# Gamecube3.net
KiCad netlist of a schematic drawn in EAGLE
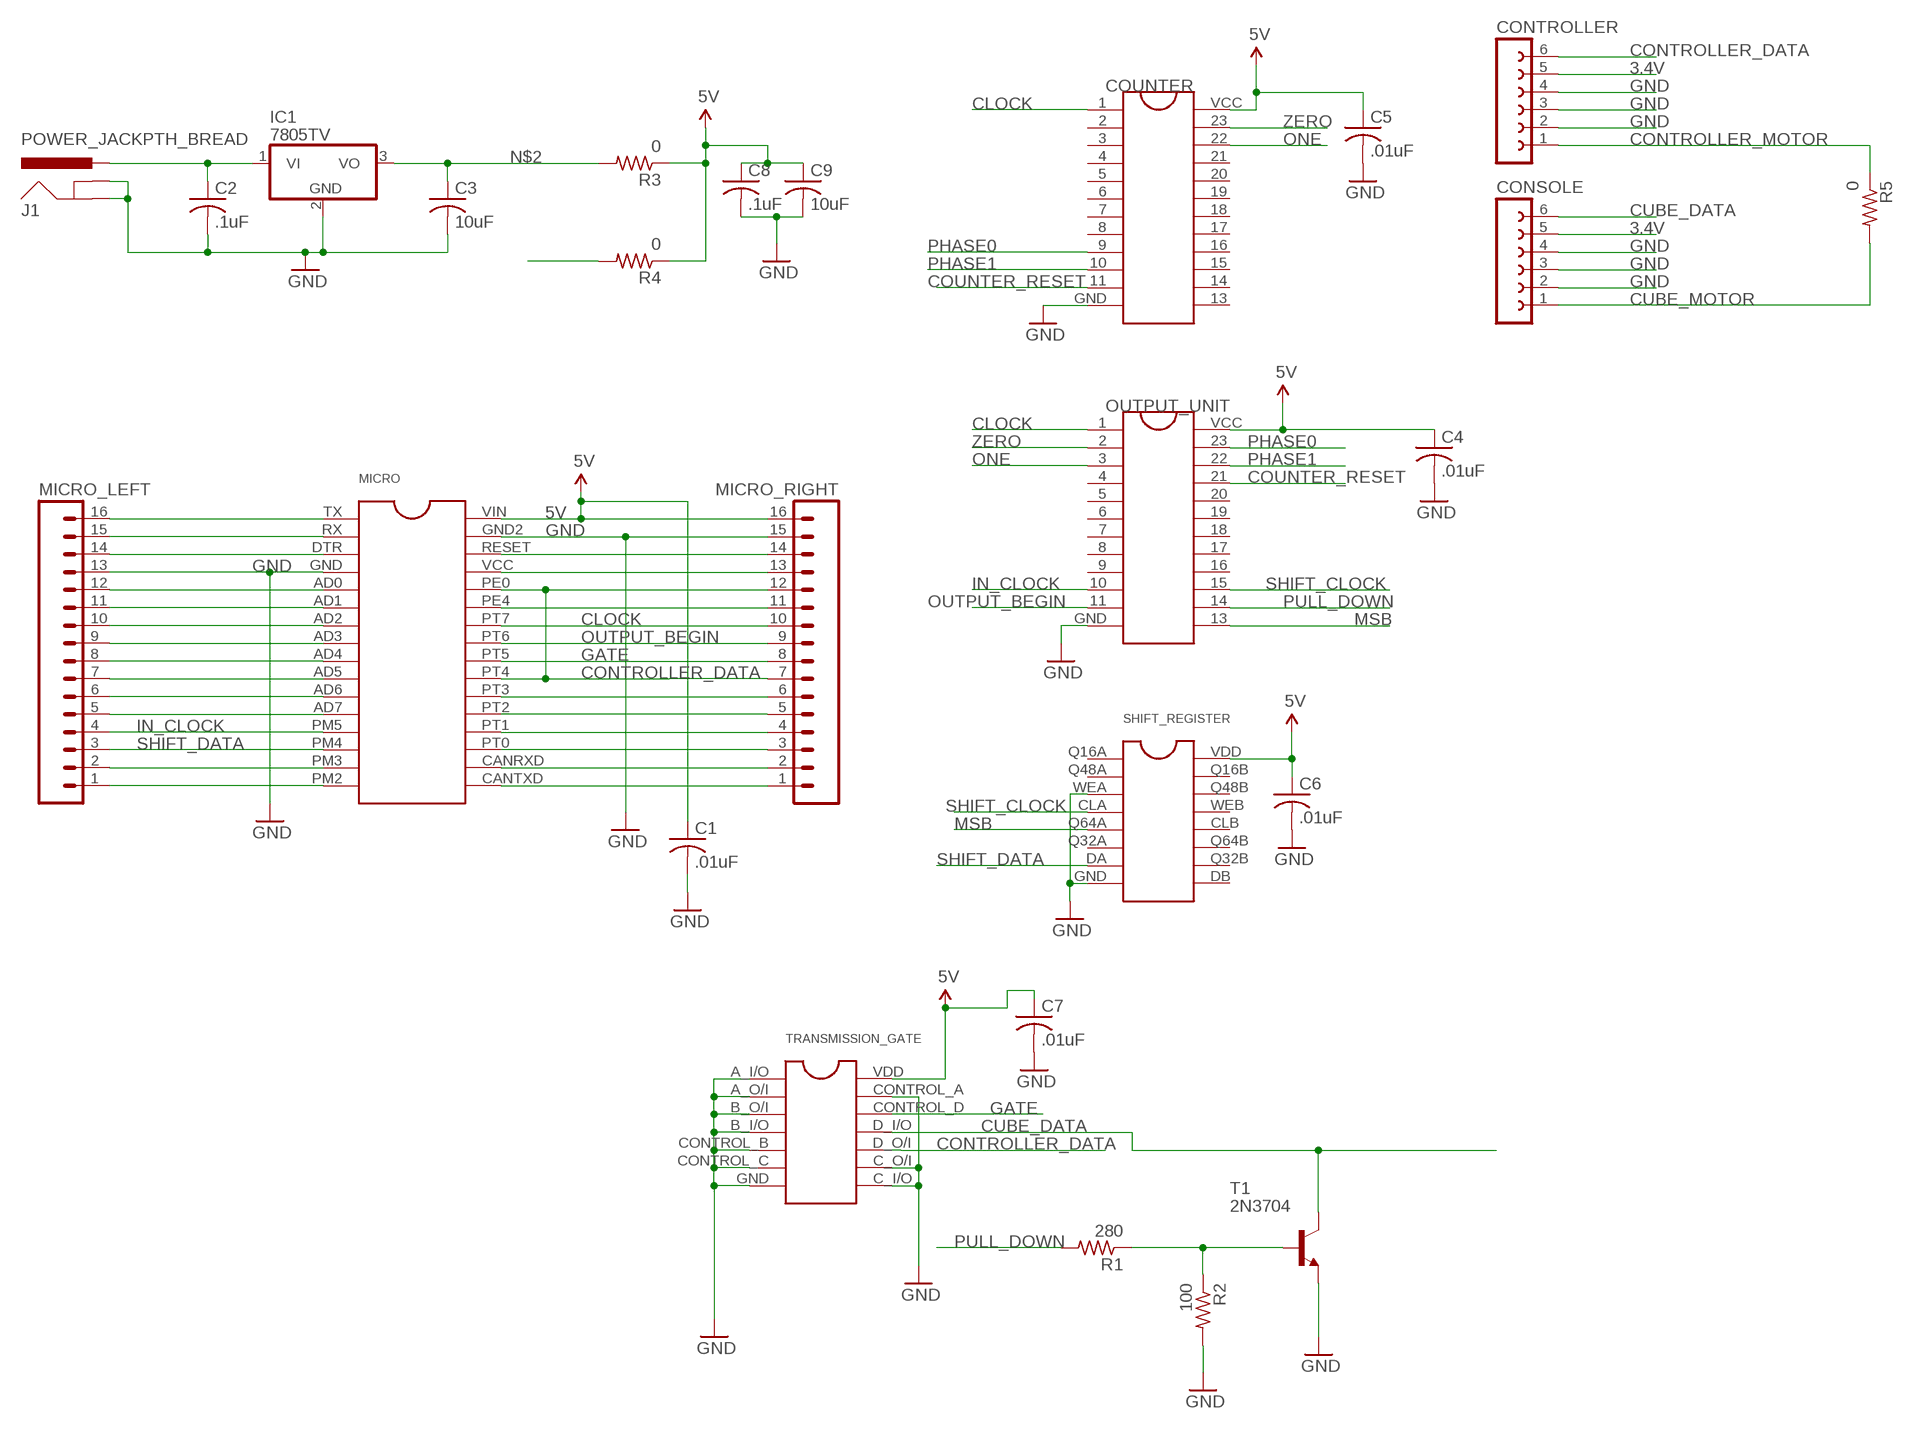
[diagram p0: schematic, sheet 1]

(export (version "E")
  (design (tool "Eeschema 10.0.6"))
  (components
    (comp (ref "C1")
      (value ".01uF")
      (footprint "eagle-import:C0805")
      (libsource (lib "eagle-import") (part "C-USC0805"))
    )
    (comp (ref "C2")
      (value ".1uF")
      (footprint "eagle-import:C0805")
      (libsource (lib "eagle-import") (part "C-USC0805"))
    )
    (comp (ref "C3")
      (value "10uF")
      (footprint "eagle-import:C1206")
      (libsource (lib "eagle-import") (part "C-USC1206"))
    )
    (comp (ref "C4")
      (value ".01uF")
      (footprint "eagle-import:C0805")
      (libsource (lib "eagle-import") (part "C-USC0805"))
    )
    (comp (ref "C5")
      (value ".01uF")
      (footprint "eagle-import:C0805")
      (libsource (lib "eagle-import") (part "C-USC0805"))
    )
    (comp (ref "C6")
      (value ".01uF")
      (footprint "eagle-import:C0805")
      (libsource (lib "eagle-import") (part "C-USC0805"))
    )
    (comp (ref "C7")
      (value ".01uF")
      (footprint "eagle-import:C0805")
      (libsource (lib "eagle-import") (part "C-USC0805"))
    )
    (comp (ref "C8")
      (value ".1uF")
      (footprint "eagle-import:C0805")
      (libsource (lib "eagle-import") (part "C-USC0805"))
    )
    (comp (ref "C9")
      (value "10uF")
      (footprint "eagle-import:C1206")
      (libsource (lib "eagle-import") (part "C-USC1206"))
    )
    (comp (ref "CONSOLE")
      (value "FE06-1")
      (footprint "eagle-import:FE06")
      (libsource (lib "eagle-import") (part "FE06-1"))
    )
    (comp (ref "CONTROLLER")
      (value "FE06-1")
      (footprint "eagle-import:FE06")
      (libsource (lib "eagle-import") (part "FE06-1"))
    )
    (comp (ref "COUNTER")
      (value "GAL22V10")
      (footprint "eagle-import:24-PIN-DIP")
      (libsource (lib "eagle-import") (part "GAL22V10"))
    )
    (comp (ref "IC1")
      (value "7805TV")
      (footprint "eagle-import:TO220V")
      (libsource (lib "eagle-import") (part "78TV05"))
    )
    (comp (ref "J1")
      (value "POWER_JACKPTH_BREAD")
      (footprint "eagle-import:POWER_JACK_PTH_BREAD")
      (libsource (lib "eagle-import") (part "POWER_JACKPTH_BREAD"))
    )
    (comp (ref "MICRO")
      (value "9S12C32")
      (footprint "eagle-import:9S12-32PIN-DIP")
      (libsource (lib "eagle-import") (part "9S12C32"))
    )
    (comp (ref "MICRO_LEFT")
      (value "M16")
      (footprint "eagle-import:16P")
      (libsource (lib "eagle-import") (part "M16"))
    )
    (comp (ref "MICRO_RIGHT")
      (value "M16")
      (footprint "eagle-import:16P")
      (libsource (lib "eagle-import") (part "M16"))
    )
    (comp (ref "OUTPUT_UNIT")
      (value "GAL22V10")
      (footprint "eagle-import:24-PIN-DIP")
      (libsource (lib "eagle-import") (part "GAL22V10"))
    )
    (comp (ref "R1")
      (value "280")
      (footprint "eagle-import:0204_7")
      (libsource (lib "eagle-import") (part "R-US_0204/7"))
    )
    (comp (ref "R2")
      (value "100")
      (footprint "eagle-import:0204_7")
      (libsource (lib "eagle-import") (part "R-US_0204/7"))
    )
    (comp (ref "R3")
      (value "0")
      (footprint "eagle-import:0204_7")
      (libsource (lib "eagle-import") (part "R-US_0204/7"))
    )
    (comp (ref "R4")
      (value "0")
      (footprint "eagle-import:0204_7")
      (libsource (lib "eagle-import") (part "R-US_0204/7"))
    )
    (comp (ref "R5")
      (value "0")
      (footprint "eagle-import:0204_7")
      (libsource (lib "eagle-import") (part "R-US_0204/7"))
    )
    (comp (ref "SHIFT_REGISTER")
      (value "CD4517B")
      (footprint "eagle-import:CD4517B")
      (libsource (lib "eagle-import") (part "CD4517B"))
    )
    (comp (ref "T1")
      (value "2N3704")
      (footprint "eagle-import:TO92")
      (libsource (lib "eagle-import") (part "2N3704"))
    )
    (comp (ref "TRANSMISSION_GATE")
      (value "CD4066B")
      (footprint "eagle-import:CD4066B")
      (libsource (lib "eagle-import") (part "CD4066B"))
    )
  )
  (nets
    (net (code "1") (name "/3.4V") (class "Default")
      (node (ref "CONSOLE") (pin "5") (pinfunction "5_5") (pintype "passive"))
      (node (ref "CONTROLLER") (pin "5") (pinfunction "5_5") (pintype "passive"))
    )
    (net (code "2") (name "/CLOCK") (class "Default")
      (node (ref "COUNTER") (pin "1") (pinfunction "1_1") (pintype "bidirectional"))
      (node (ref "MICRO") (pin "PT7") (pinfunction "P$26_PT7") (pintype "bidirectional"))
      (node (ref "MICRO_RIGHT") (pin "10") (pinfunction "10_10") (pintype "passive"))
      (node (ref "OUTPUT_UNIT") (pin "1") (pinfunction "1_1") (pintype "bidirectional"))
    )
    (net (code "3") (name "/CONTROLLER_DATA") (class "Default")
      (node (ref "CONTROLLER") (pin "6") (pinfunction "6_6") (pintype "passive"))
      (node (ref "MICRO") (pin "PE0") (pinfunction "P$28_PE0") (pintype "bidirectional"))
      (node (ref "MICRO") (pin "PT4") (pinfunction "P$23_PT4") (pintype "bidirectional"))
      (node (ref "MICRO_RIGHT") (pin "12") (pinfunction "12_12") (pintype "passive"))
      (node (ref "MICRO_RIGHT") (pin "7") (pinfunction "7_7") (pintype "passive"))
      (node (ref "TRANSMISSION_GATE") (pin "D_O/I") (pinfunction "P$10_D_O/I") (pintype "bidirectional"))
    )
    (net (code "4") (name "/CONTROLLER_MOTOR") (class "Default")
      (node (ref "CONTROLLER") (pin "1") (pinfunction "1_1") (pintype "passive"))
      (node (ref "R5") (pin "1") (pinfunction "1_1") (pintype "passive"))
    )
    (net (code "5") (name "/COUNTER_RESET") (class "Default")
      (node (ref "COUNTER") (pin "11") (pinfunction "11_11") (pintype "bidirectional"))
      (node (ref "OUTPUT_UNIT") (pin "21") (pinfunction "21_21") (pintype "bidirectional"))
    )
    (net (code "6") (name "/CUBE_DATA") (class "Default")
      (node (ref "CONSOLE") (pin "6") (pinfunction "6_6") (pintype "passive"))
      (node (ref "T1") (pin "2") (pinfunction "C_2") (pintype "passive"))
      (node (ref "TRANSMISSION_GATE") (pin "D_I/O") (pinfunction "P$11_D_I/O") (pintype "bidirectional"))
    )
    (net (code "7") (name "/CUBE_MOTOR") (class "Default")
      (node (ref "CONSOLE") (pin "1") (pinfunction "1_1") (pintype "passive"))
      (node (ref "R4") (pin "2") (pinfunction "2_2") (pintype "passive"))
      (node (ref "R5") (pin "2") (pinfunction "2_2") (pintype "passive"))
    )
    (net (code "8") (name "/GATE") (class "Default")
      (node (ref "MICRO") (pin "PT5") (pinfunction "P$24_PT5") (pintype "bidirectional"))
      (node (ref "MICRO_RIGHT") (pin "8") (pinfunction "8_8") (pintype "passive"))
      (node (ref "TRANSMISSION_GATE") (pin "CONTROL_D") (pinfunction "P$12_CONTROL_D") (pintype "bidirectional"))
    )
    (net (code "9") (name "/IN_CLOCK") (class "Default")
      (node (ref "MICRO") (pin "PM5") (pinfunction "P$13_PM5") (pintype "bidirectional"))
      (node (ref "MICRO_LEFT") (pin "4") (pinfunction "4_4") (pintype "passive"))
      (node (ref "OUTPUT_UNIT") (pin "10") (pinfunction "10_10") (pintype "bidirectional"))
    )
    (net (code "10") (name "/MSB") (class "Default")
      (node (ref "OUTPUT_UNIT") (pin "13") (pinfunction "13_13") (pintype "bidirectional"))
      (node (ref "SHIFT_REGISTER") (pin "Q64A") (pinfunction "P$5_Q64A") (pintype "bidirectional"))
    )
    (net (code "11") (name "/N$2") (class "Default")
      (node (ref "C3") (pin "1") (pinfunction "1_1") (pintype "passive"))
      (node (ref "IC1") (pin "3") (pinfunction "VO_3") (pintype "passive"))
      (node (ref "R3") (pin "2") (pinfunction "2_2") (pintype "passive"))
    )
    (net (code "12") (name "/ONE") (class "Default")
      (node (ref "COUNTER") (pin "22") (pinfunction "22_22") (pintype "bidirectional"))
      (node (ref "OUTPUT_UNIT") (pin "3") (pinfunction "3_3") (pintype "bidirectional"))
    )
    (net (code "13") (name "/OUTPUT_BEGIN") (class "Default")
      (node (ref "MICRO") (pin "PT6") (pinfunction "P$25_PT6") (pintype "bidirectional"))
      (node (ref "MICRO_RIGHT") (pin "9") (pinfunction "9_9") (pintype "passive"))
      (node (ref "OUTPUT_UNIT") (pin "11") (pinfunction "11_11") (pintype "bidirectional"))
    )
    (net (code "14") (name "/PHASE0") (class "Default")
      (node (ref "COUNTER") (pin "9") (pinfunction "9_9") (pintype "bidirectional"))
      (node (ref "OUTPUT_UNIT") (pin "23") (pinfunction "23_23") (pintype "bidirectional"))
    )
    (net (code "15") (name "/PHASE1") (class "Default")
      (node (ref "COUNTER") (pin "10") (pinfunction "10_10") (pintype "bidirectional"))
      (node (ref "OUTPUT_UNIT") (pin "22") (pinfunction "22_22") (pintype "bidirectional"))
    )
    (net (code "16") (name "/PULL_DOWN") (class "Default")
      (node (ref "OUTPUT_UNIT") (pin "14") (pinfunction "14_14") (pintype "bidirectional"))
      (node (ref "R1") (pin "2") (pinfunction "2_2") (pintype "passive"))
    )
    (net (code "17") (name "/SHIFT_CLOCK") (class "Default")
      (node (ref "OUTPUT_UNIT") (pin "15") (pinfunction "15_15") (pintype "bidirectional"))
      (node (ref "SHIFT_REGISTER") (pin "CLA") (pinfunction "P$4_CLA") (pintype "bidirectional"))
    )
    (net (code "18") (name "/SHIFT_DATA") (class "Default")
      (node (ref "MICRO") (pin "PM4") (pinfunction "P$14_PM4") (pintype "bidirectional"))
      (node (ref "MICRO_LEFT") (pin "3") (pinfunction "3_3") (pintype "passive"))
      (node (ref "SHIFT_REGISTER") (pin "DA") (pinfunction "P$7_DA") (pintype "bidirectional"))
    )
    (net (code "19") (name "/ZERO") (class "Default")
      (node (ref "COUNTER") (pin "23") (pinfunction "23_23") (pintype "bidirectional"))
      (node (ref "OUTPUT_UNIT") (pin "2") (pinfunction "2_2") (pintype "bidirectional"))
    )
    (net (code "20") (name "5V") (class "Default")
      (node (ref "C1") (pin "1") (pinfunction "1_1") (pintype "passive"))
      (node (ref "C4") (pin "1") (pinfunction "1_1") (pintype "passive"))
      (node (ref "C5") (pin "1") (pinfunction "1_1") (pintype "passive"))
      (node (ref "C6") (pin "1") (pinfunction "1_1") (pintype "passive"))
      (node (ref "C7") (pin "1") (pinfunction "1_1") (pintype "passive"))
      (node (ref "C8") (pin "1") (pinfunction "1_1") (pintype "passive"))
      (node (ref "C9") (pin "1") (pinfunction "1_1") (pintype "passive"))
      (node (ref "COUNTER") (pin "VCC") (pinfunction "VCC_VCC") (pintype "bidirectional"))
      (node (ref "MICRO") (pin "VIN") (pinfunction "P$32_VIN") (pintype "bidirectional"))
      (node (ref "MICRO_RIGHT") (pin "16") (pinfunction "16_16") (pintype "passive"))
      (node (ref "OUTPUT_UNIT") (pin "VCC") (pinfunction "VCC_VCC") (pintype "bidirectional"))
      (node (ref "R3") (pin "1") (pinfunction "1_1") (pintype "passive"))
      (node (ref "R4") (pin "1") (pinfunction "1_1") (pintype "passive"))
      (node (ref "SHIFT_REGISTER") (pin "VDD") (pinfunction "P$16_VDD") (pintype "bidirectional"))
      (node (ref "TRANSMISSION_GATE") (pin "VDD") (pinfunction "P$14_VDD") (pintype "bidirectional"))
    )
    (net (code "21") (name "GND") (class "Default")
      (node (ref "C1") (pin "2") (pinfunction "2_2") (pintype "passive"))
      (node (ref "C2") (pin "2") (pinfunction "2_2") (pintype "passive"))
      (node (ref "C3") (pin "2") (pinfunction "2_2") (pintype "passive"))
      (node (ref "C4") (pin "2") (pinfunction "2_2") (pintype "passive"))
      (node (ref "C5") (pin "2") (pinfunction "2_2") (pintype "passive"))
      (node (ref "C6") (pin "2") (pinfunction "2_2") (pintype "passive"))
      (node (ref "C7") (pin "2") (pinfunction "2_2") (pintype "passive"))
      (node (ref "C8") (pin "2") (pinfunction "2_2") (pintype "passive"))
      (node (ref "C9") (pin "2") (pinfunction "2_2") (pintype "passive"))
      (node (ref "CONSOLE") (pin "2") (pinfunction "2_2") (pintype "passive"))
      (node (ref "CONSOLE") (pin "3") (pinfunction "3_3") (pintype "passive"))
      (node (ref "CONSOLE") (pin "4") (pinfunction "4_4") (pintype "passive"))
      (node (ref "CONTROLLER") (pin "2") (pinfunction "2_2") (pintype "passive"))
      (node (ref "CONTROLLER") (pin "3") (pinfunction "3_3") (pintype "passive"))
      (node (ref "CONTROLLER") (pin "4") (pinfunction "4_4") (pintype "passive"))
      (node (ref "COUNTER") (pin "GND") (pinfunction "GND_GND") (pintype "bidirectional"))
      (node (ref "IC1") (pin "2") (pinfunction "GND_2") (pintype "passive"))
      (node (ref "J1") (pin "GND") (pinfunction "GND_GND") (pintype "bidirectional"))
      (node (ref "J1") (pin "GNDBREAK") (pinfunction "GNDBREAK_GNDBREAK") (pintype "bidirectional"))
      (node (ref "MICRO") (pin "GND") (pinfunction "P$4_GND") (pintype "bidirectional"))
      (node (ref "MICRO") (pin "GND2") (pinfunction "P$31_GND2") (pintype "bidirectional"))
      (node (ref "MICRO_LEFT") (pin "13") (pinfunction "13_13") (pintype "passive"))
      (node (ref "MICRO_RIGHT") (pin "15") (pinfunction "15_15") (pintype "passive"))
      (node (ref "OUTPUT_UNIT") (pin "GND") (pinfunction "GND_GND") (pintype "bidirectional"))
      (node (ref "R2") (pin "2") (pinfunction "2_2") (pintype "passive"))
      (node (ref "SHIFT_REGISTER") (pin "GND") (pinfunction "P$8_GND") (pintype "bidirectional"))
      (node (ref "SHIFT_REGISTER") (pin "WEA") (pinfunction "P$3_WEA") (pintype "bidirectional"))
      (node (ref "T1") (pin "3") (pinfunction "E_3") (pintype "passive"))
      (node (ref "TRANSMISSION_GATE") (pin "A_I/O") (pinfunction "P$1_A_I/O") (pintype "bidirectional"))
      (node (ref "TRANSMISSION_GATE") (pin "A_O/I") (pinfunction "P$2_A_O/I") (pintype "bidirectional"))
      (node (ref "TRANSMISSION_GATE") (pin "B_I/O") (pinfunction "P$4_B_I/O") (pintype "bidirectional"))
      (node (ref "TRANSMISSION_GATE") (pin "B_O/I") (pinfunction "P$3_B_O/I") (pintype "bidirectional"))
      (node (ref "TRANSMISSION_GATE") (pin "CONTROL_A") (pinfunction "P$13_CONTROL_A") (pintype "bidirectional"))
      (node (ref "TRANSMISSION_GATE") (pin "CONTROL_B") (pinfunction "P$5_CONTROL_B") (pintype "bidirectional"))
      (node (ref "TRANSMISSION_GATE") (pin "CONTROL_C") (pinfunction "P$6_CONTROL_C") (pintype "bidirectional"))
      (node (ref "TRANSMISSION_GATE") (pin "C_I/O") (pinfunction "P$8_C_I/O") (pintype "bidirectional"))
      (node (ref "TRANSMISSION_GATE") (pin "C_O/I") (pinfunction "P$9_C_O/I") (pintype "bidirectional"))
      (node (ref "TRANSMISSION_GATE") (pin "GND") (pinfunction "P$7_GND") (pintype "bidirectional"))
    )
    (net (code "22") (name "Net-(IC1-VI)") (class "Default")
      (node (ref "C2") (pin "1") (pinfunction "1_1") (pintype "passive"))
      (node (ref "IC1") (pin "1") (pinfunction "VI_1") (pintype "input"))
      (node (ref "J1") (pin "PWR") (pinfunction "PWR_PWR") (pintype "bidirectional"))
    )
    (net (code "23") (name "Net-(MICRO-P$1)") (class "Default")
      (node (ref "MICRO") (pin "TX") (pinfunction "P$1_TX") (pintype "bidirectional"))
      (node (ref "MICRO_LEFT") (pin "16") (pinfunction "16_16") (pintype "passive"))
    )
    (net (code "24") (name "Net-(MICRO-P$2)") (class "Default")
      (node (ref "MICRO") (pin "RX") (pinfunction "P$2_RX") (pintype "bidirectional"))
      (node (ref "MICRO_LEFT") (pin "15") (pinfunction "15_15") (pintype "passive"))
    )
    (net (code "25") (name "Net-(MICRO-P$3)") (class "Default")
      (node (ref "MICRO") (pin "DTR") (pinfunction "P$3_DTR") (pintype "bidirectional"))
      (node (ref "MICRO_LEFT") (pin "14") (pinfunction "14_14") (pintype "passive"))
    )
    (net (code "26") (name "Net-(MICRO-P$5)") (class "Default")
      (node (ref "MICRO") (pin "AD0") (pinfunction "P$5_AD0") (pintype "bidirectional"))
      (node (ref "MICRO_LEFT") (pin "12") (pinfunction "12_12") (pintype "passive"))
    )
    (net (code "27") (name "Net-(MICRO-P$6)") (class "Default")
      (node (ref "MICRO") (pin "AD1") (pinfunction "P$6_AD1") (pintype "bidirectional"))
      (node (ref "MICRO_LEFT") (pin "11") (pinfunction "11_11") (pintype "passive"))
    )
    (net (code "28") (name "Net-(MICRO-P$7)") (class "Default")
      (node (ref "MICRO") (pin "AD2") (pinfunction "P$7_AD2") (pintype "bidirectional"))
      (node (ref "MICRO_LEFT") (pin "10") (pinfunction "10_10") (pintype "passive"))
    )
    (net (code "29") (name "Net-(MICRO-P$8)") (class "Default")
      (node (ref "MICRO") (pin "AD3") (pinfunction "P$8_AD3") (pintype "bidirectional"))
      (node (ref "MICRO_LEFT") (pin "9") (pinfunction "9_9") (pintype "passive"))
    )
    (net (code "30") (name "Net-(MICRO-P$9)") (class "Default")
      (node (ref "MICRO") (pin "AD4") (pinfunction "P$9_AD4") (pintype "bidirectional"))
      (node (ref "MICRO_LEFT") (pin "8") (pinfunction "8_8") (pintype "passive"))
    )
    (net (code "31") (name "Net-(MICRO-P$10)") (class "Default")
      (node (ref "MICRO") (pin "AD5") (pinfunction "P$10_AD5") (pintype "bidirectional"))
      (node (ref "MICRO_LEFT") (pin "7") (pinfunction "7_7") (pintype "passive"))
    )
    (net (code "32") (name "Net-(MICRO-P$11)") (class "Default")
      (node (ref "MICRO") (pin "AD6") (pinfunction "P$11_AD6") (pintype "bidirectional"))
      (node (ref "MICRO_LEFT") (pin "6") (pinfunction "6_6") (pintype "passive"))
    )
    (net (code "33") (name "Net-(MICRO-P$12)") (class "Default")
      (node (ref "MICRO") (pin "AD7") (pinfunction "P$12_AD7") (pintype "bidirectional"))
      (node (ref "MICRO_LEFT") (pin "5") (pinfunction "5_5") (pintype "passive"))
    )
    (net (code "34") (name "Net-(MICRO-P$15)") (class "Default")
      (node (ref "MICRO") (pin "PM3") (pinfunction "P$15_PM3") (pintype "bidirectional"))
      (node (ref "MICRO_LEFT") (pin "2") (pinfunction "2_2") (pintype "passive"))
    )
    (net (code "35") (name "Net-(MICRO-P$16)") (class "Default")
      (node (ref "MICRO") (pin "PM2") (pinfunction "P$16_PM2") (pintype "bidirectional"))
      (node (ref "MICRO_LEFT") (pin "1") (pinfunction "1_1") (pintype "passive"))
    )
    (net (code "36") (name "Net-(MICRO-P$17)") (class "Default")
      (node (ref "MICRO") (pin "CANTXD") (pinfunction "P$17_CANTXD") (pintype "bidirectional"))
      (node (ref "MICRO_RIGHT") (pin "1") (pinfunction "1_1") (pintype "passive"))
    )
    (net (code "37") (name "Net-(MICRO-P$18)") (class "Default")
      (node (ref "MICRO") (pin "CANRXD") (pinfunction "P$18_CANRXD") (pintype "bidirectional"))
      (node (ref "MICRO_RIGHT") (pin "2") (pinfunction "2_2") (pintype "passive"))
    )
    (net (code "38") (name "Net-(MICRO-P$19)") (class "Default")
      (node (ref "MICRO") (pin "PT0") (pinfunction "P$19_PT0") (pintype "bidirectional"))
      (node (ref "MICRO_RIGHT") (pin "3") (pinfunction "3_3") (pintype "passive"))
    )
    (net (code "39") (name "Net-(MICRO-P$20)") (class "Default")
      (node (ref "MICRO") (pin "PT1") (pinfunction "P$20_PT1") (pintype "bidirectional"))
      (node (ref "MICRO_RIGHT") (pin "4") (pinfunction "4_4") (pintype "passive"))
    )
    (net (code "40") (name "Net-(MICRO-P$21)") (class "Default")
      (node (ref "MICRO") (pin "PT2") (pinfunction "P$21_PT2") (pintype "bidirectional"))
      (node (ref "MICRO_RIGHT") (pin "5") (pinfunction "5_5") (pintype "passive"))
    )
    (net (code "41") (name "Net-(MICRO-P$22)") (class "Default")
      (node (ref "MICRO") (pin "PT3") (pinfunction "P$22_PT3") (pintype "bidirectional"))
      (node (ref "MICRO_RIGHT") (pin "6") (pinfunction "6_6") (pintype "passive"))
    )
    (net (code "42") (name "Net-(MICRO-P$27)") (class "Default")
      (node (ref "MICRO") (pin "PE4") (pinfunction "P$27_PE4") (pintype "bidirectional"))
      (node (ref "MICRO_RIGHT") (pin "11") (pinfunction "11_11") (pintype "passive"))
    )
    (net (code "43") (name "Net-(MICRO-P$29)") (class "Default")
      (node (ref "MICRO") (pin "VCC") (pinfunction "P$29_VCC") (pintype "bidirectional"))
      (node (ref "MICRO_RIGHT") (pin "13") (pinfunction "13_13") (pintype "passive"))
    )
    (net (code "44") (name "Net-(MICRO-P$30)") (class "Default")
      (node (ref "MICRO") (pin "RESET") (pinfunction "P$30_RESET") (pintype "bidirectional"))
      (node (ref "MICRO_RIGHT") (pin "14") (pinfunction "14_14") (pintype "passive"))
    )
    (net (code "45") (name "Net-(T1-B)") (class "Default")
      (node (ref "R1") (pin "1") (pinfunction "1_1") (pintype "passive"))
      (node (ref "R2") (pin "1") (pinfunction "1_1") (pintype "passive"))
      (node (ref "T1") (pin "1") (pinfunction "B_1") (pintype "passive"))
    )
    (net (code "46") (name "unconnected-(COUNTER-Pad2)") (class "Default")
      (node (ref "COUNTER") (pin "2") (pinfunction "2_2") (pintype "bidirectional"))
    )
    (net (code "47") (name "unconnected-(COUNTER-Pad3)") (class "Default")
      (node (ref "COUNTER") (pin "3") (pinfunction "3_3") (pintype "bidirectional"))
    )
    (net (code "48") (name "unconnected-(COUNTER-Pad4)") (class "Default")
      (node (ref "COUNTER") (pin "4") (pinfunction "4_4") (pintype "bidirectional"))
    )
    (net (code "49") (name "unconnected-(COUNTER-Pad5)") (class "Default")
      (node (ref "COUNTER") (pin "5") (pinfunction "5_5") (pintype "bidirectional"))
    )
    (net (code "50") (name "unconnected-(COUNTER-Pad6)") (class "Default")
      (node (ref "COUNTER") (pin "6") (pinfunction "6_6") (pintype "bidirectional"))
    )
    (net (code "51") (name "unconnected-(COUNTER-Pad7)") (class "Default")
      (node (ref "COUNTER") (pin "7") (pinfunction "7_7") (pintype "bidirectional"))
    )
    (net (code "52") (name "unconnected-(COUNTER-Pad8)") (class "Default")
      (node (ref "COUNTER") (pin "8") (pinfunction "8_8") (pintype "bidirectional"))
    )
    (net (code "53") (name "unconnected-(COUNTER-Pad13)") (class "Default")
      (node (ref "COUNTER") (pin "13") (pinfunction "13_13") (pintype "bidirectional"))
    )
    (net (code "54") (name "unconnected-(COUNTER-Pad14)") (class "Default")
      (node (ref "COUNTER") (pin "14") (pinfunction "14_14") (pintype "bidirectional"))
    )
    (net (code "55") (name "unconnected-(COUNTER-Pad15)") (class "Default")
      (node (ref "COUNTER") (pin "15") (pinfunction "15_15") (pintype "bidirectional"))
    )
    (net (code "56") (name "unconnected-(COUNTER-Pad16)") (class "Default")
      (node (ref "COUNTER") (pin "16") (pinfunction "16_16") (pintype "bidirectional"))
    )
    (net (code "57") (name "unconnected-(COUNTER-Pad17)") (class "Default")
      (node (ref "COUNTER") (pin "17") (pinfunction "17_17") (pintype "bidirectional"))
    )
    (net (code "58") (name "unconnected-(COUNTER-Pad18)") (class "Default")
      (node (ref "COUNTER") (pin "18") (pinfunction "18_18") (pintype "bidirectional"))
    )
    (net (code "59") (name "unconnected-(COUNTER-Pad19)") (class "Default")
      (node (ref "COUNTER") (pin "19") (pinfunction "19_19") (pintype "bidirectional"))
    )
    (net (code "60") (name "unconnected-(COUNTER-Pad20)") (class "Default")
      (node (ref "COUNTER") (pin "20") (pinfunction "20_20") (pintype "bidirectional"))
    )
    (net (code "61") (name "unconnected-(COUNTER-Pad21)") (class "Default")
      (node (ref "COUNTER") (pin "21") (pinfunction "21_21") (pintype "bidirectional"))
    )
    (net (code "62") (name "unconnected-(OUTPUT_UNIT-Pad4)") (class "Default")
      (node (ref "OUTPUT_UNIT") (pin "4") (pinfunction "4_4") (pintype "bidirectional"))
    )
    (net (code "63") (name "unconnected-(OUTPUT_UNIT-Pad5)") (class "Default")
      (node (ref "OUTPUT_UNIT") (pin "5") (pinfunction "5_5") (pintype "bidirectional"))
    )
    (net (code "64") (name "unconnected-(OUTPUT_UNIT-Pad6)") (class "Default")
      (node (ref "OUTPUT_UNIT") (pin "6") (pinfunction "6_6") (pintype "bidirectional"))
    )
    (net (code "65") (name "unconnected-(OUTPUT_UNIT-Pad7)") (class "Default")
      (node (ref "OUTPUT_UNIT") (pin "7") (pinfunction "7_7") (pintype "bidirectional"))
    )
    (net (code "66") (name "unconnected-(OUTPUT_UNIT-Pad8)") (class "Default")
      (node (ref "OUTPUT_UNIT") (pin "8") (pinfunction "8_8") (pintype "bidirectional"))
    )
    (net (code "67") (name "unconnected-(OUTPUT_UNIT-Pad9)") (class "Default")
      (node (ref "OUTPUT_UNIT") (pin "9") (pinfunction "9_9") (pintype "bidirectional"))
    )
    (net (code "68") (name "unconnected-(OUTPUT_UNIT-Pad16)") (class "Default")
      (node (ref "OUTPUT_UNIT") (pin "16") (pinfunction "16_16") (pintype "bidirectional"))
    )
    (net (code "69") (name "unconnected-(OUTPUT_UNIT-Pad17)") (class "Default")
      (node (ref "OUTPUT_UNIT") (pin "17") (pinfunction "17_17") (pintype "bidirectional"))
    )
    (net (code "70") (name "unconnected-(OUTPUT_UNIT-Pad18)") (class "Default")
      (node (ref "OUTPUT_UNIT") (pin "18") (pinfunction "18_18") (pintype "bidirectional"))
    )
    (net (code "71") (name "unconnected-(OUTPUT_UNIT-Pad19)") (class "Default")
      (node (ref "OUTPUT_UNIT") (pin "19") (pinfunction "19_19") (pintype "bidirectional"))
    )
    (net (code "72") (name "unconnected-(OUTPUT_UNIT-Pad20)") (class "Default")
      (node (ref "OUTPUT_UNIT") (pin "20") (pinfunction "20_20") (pintype "bidirectional"))
    )
    (net (code "73") (name "unconnected-(SHIFT_REGISTER-P$1-PadQ16A)") (class "Default")
      (node (ref "SHIFT_REGISTER") (pin "Q16A") (pinfunction "P$1_Q16A") (pintype "bidirectional"))
    )
    (net (code "74") (name "unconnected-(SHIFT_REGISTER-P$2-PadQ48A)") (class "Default")
      (node (ref "SHIFT_REGISTER") (pin "Q48A") (pinfunction "P$2_Q48A") (pintype "bidirectional"))
    )
    (net (code "75") (name "unconnected-(SHIFT_REGISTER-P$6-PadQ32A)") (class "Default")
      (node (ref "SHIFT_REGISTER") (pin "Q32A") (pinfunction "P$6_Q32A") (pintype "bidirectional"))
    )
    (net (code "76") (name "unconnected-(SHIFT_REGISTER-P$9-PadDB)") (class "Default")
      (node (ref "SHIFT_REGISTER") (pin "DB") (pinfunction "P$9_DB") (pintype "bidirectional"))
    )
    (net (code "77") (name "unconnected-(SHIFT_REGISTER-P$10-PadQ32B)") (class "Default")
      (node (ref "SHIFT_REGISTER") (pin "Q32B") (pinfunction "P$10_Q32B") (pintype "bidirectional"))
    )
    (net (code "78") (name "unconnected-(SHIFT_REGISTER-P$11-PadQ64B)") (class "Default")
      (node (ref "SHIFT_REGISTER") (pin "Q64B") (pinfunction "P$11_Q64B") (pintype "bidirectional"))
    )
    (net (code "79") (name "unconnected-(SHIFT_REGISTER-P$12-PadCLB)") (class "Default")
      (node (ref "SHIFT_REGISTER") (pin "CLB") (pinfunction "P$12_CLB") (pintype "bidirectional"))
    )
    (net (code "80") (name "unconnected-(SHIFT_REGISTER-P$13-PadWEB)") (class "Default")
      (node (ref "SHIFT_REGISTER") (pin "WEB") (pinfunction "P$13_WEB") (pintype "bidirectional"))
    )
    (net (code "81") (name "unconnected-(SHIFT_REGISTER-P$14-PadQ48B)") (class "Default")
      (node (ref "SHIFT_REGISTER") (pin "Q48B") (pinfunction "P$14_Q48B") (pintype "bidirectional"))
    )
    (net (code "82") (name "unconnected-(SHIFT_REGISTER-P$15-PadQ16B)") (class "Default")
      (node (ref "SHIFT_REGISTER") (pin "Q16B") (pinfunction "P$15_Q16B") (pintype "bidirectional"))
    )
  )
)
